# dekatron-sim-4017-a2.net
KiCad netlist of a schematic drawn in EAGLE
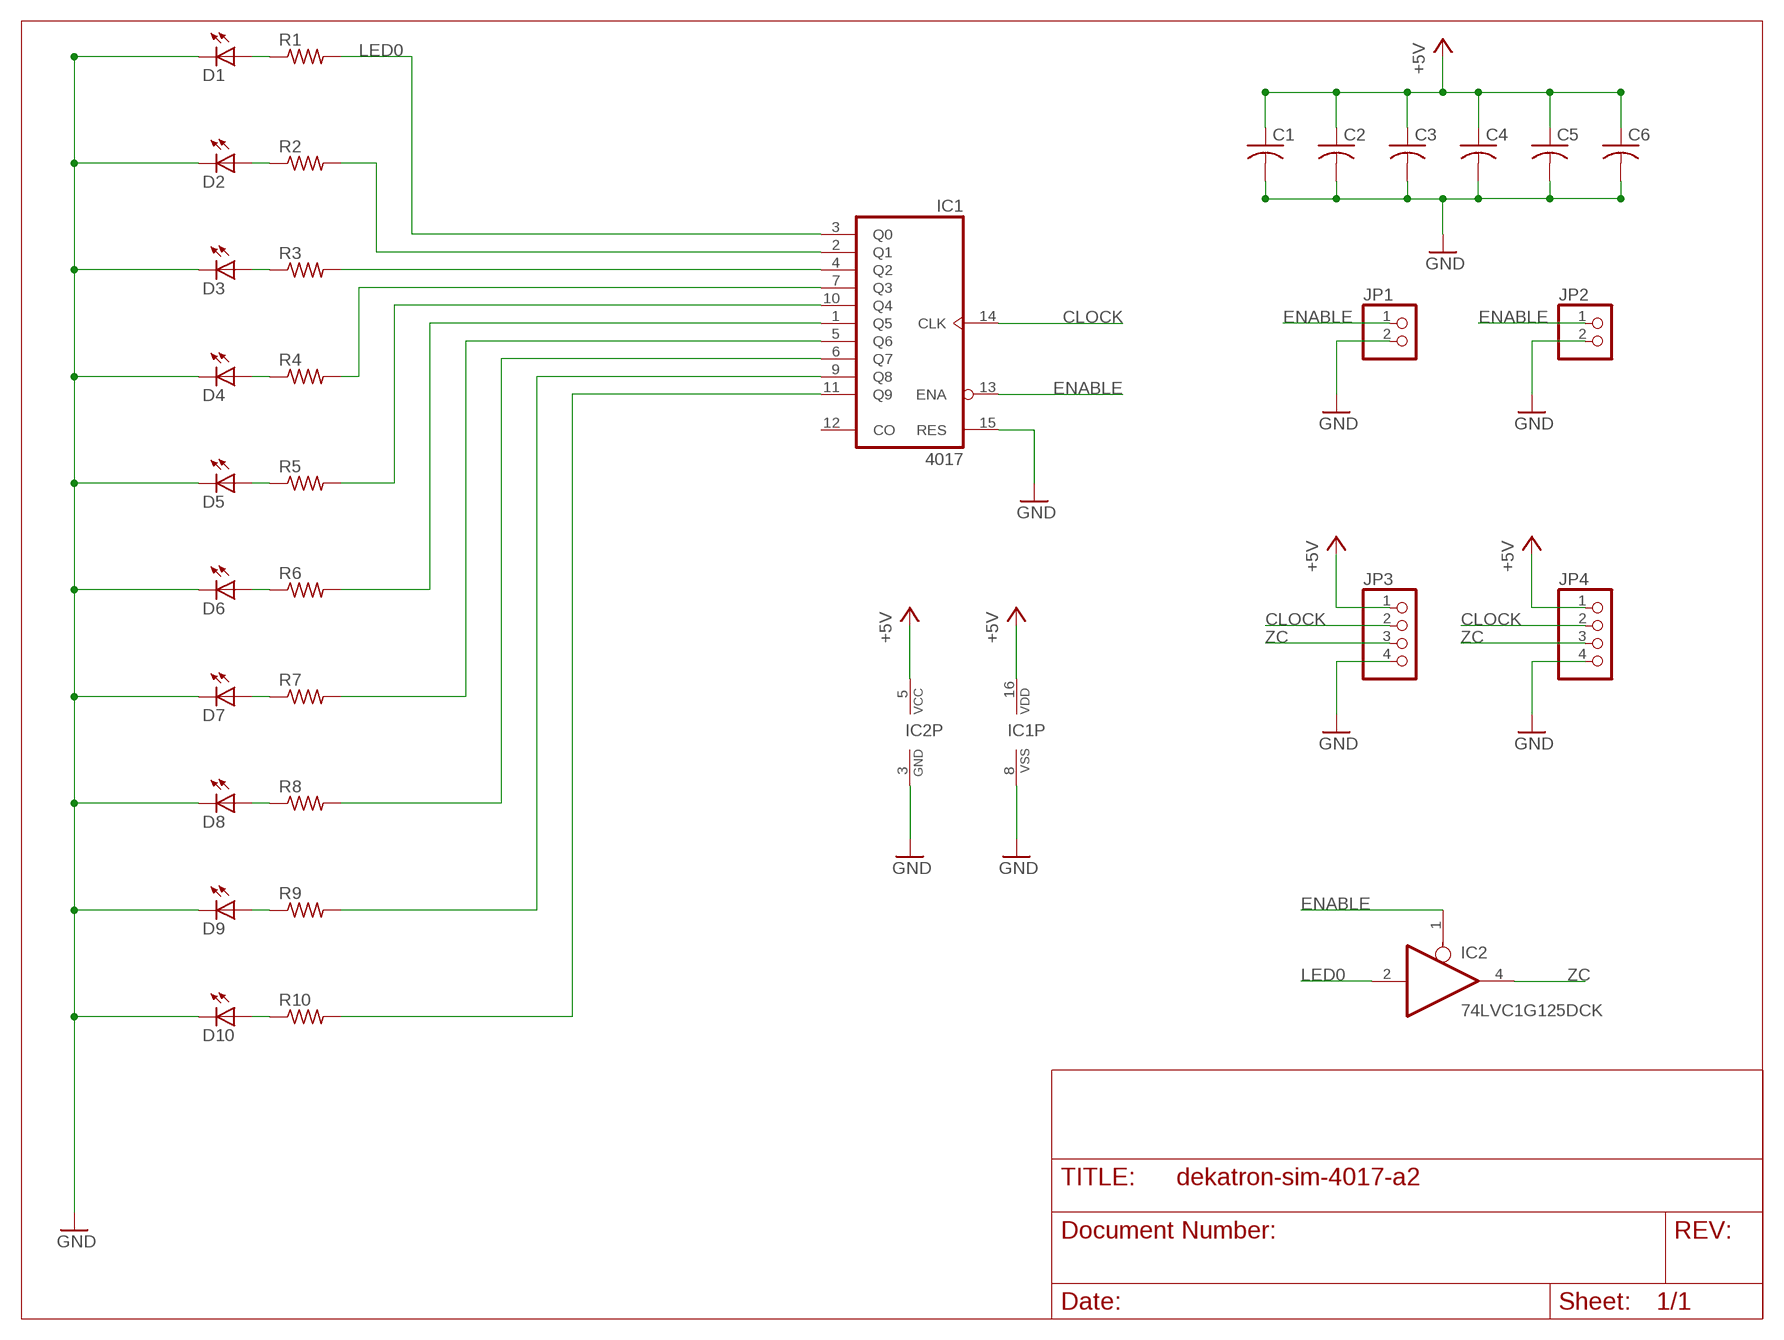
[diagram p0: schematic, sheet 1]

(export (version "E")
  (design (tool "Eeschema 10.0.6"))
  (components
    (comp (ref "C1")
      (value "C-USC0805")
      (footprint "eagle-import:C0805")
      (libsource (lib "eagle-import") (part "C-USC0805"))
    )
    (comp (ref "C2")
      (value "C-USC0805")
      (footprint "eagle-import:C0805")
      (libsource (lib "eagle-import") (part "C-USC0805"))
    )
    (comp (ref "C3")
      (value "C-USC0805")
      (footprint "eagle-import:C0805")
      (libsource (lib "eagle-import") (part "C-USC0805"))
    )
    (comp (ref "C4")
      (value "C-USC0805")
      (footprint "eagle-import:C0805")
      (libsource (lib "eagle-import") (part "C-USC0805"))
    )
    (comp (ref "C5")
      (value "C-USC0805")
      (footprint "eagle-import:C0805")
      (libsource (lib "eagle-import") (part "C-USC0805"))
    )
    (comp (ref "C6")
      (value "C-USC0805")
      (footprint "eagle-import:C0805")
      (libsource (lib "eagle-import") (part "C-USC0805"))
    )
    (comp (ref "D1")
      (value "RED")
      (footprint "eagle-import:CHIP-LED0603")
      (libsource (lib "eagle-import") (part "LEDCHIP-LED0603"))
    )
    (comp (ref "D2")
      (value "RED")
      (footprint "eagle-import:CHIP-LED0603")
      (libsource (lib "eagle-import") (part "LEDCHIP-LED0603"))
    )
    (comp (ref "D3")
      (value "RED")
      (footprint "eagle-import:CHIP-LED0603")
      (libsource (lib "eagle-import") (part "LEDCHIP-LED0603"))
    )
    (comp (ref "D4")
      (value "RED")
      (footprint "eagle-import:CHIP-LED0603")
      (libsource (lib "eagle-import") (part "LEDCHIP-LED0603"))
    )
    (comp (ref "D5")
      (value "RED")
      (footprint "eagle-import:CHIP-LED0603")
      (libsource (lib "eagle-import") (part "LEDCHIP-LED0603"))
    )
    (comp (ref "D6")
      (value "RED")
      (footprint "eagle-import:CHIP-LED0603")
      (libsource (lib "eagle-import") (part "LEDCHIP-LED0603"))
    )
    (comp (ref "D7")
      (value "RED")
      (footprint "eagle-import:CHIP-LED0603")
      (libsource (lib "eagle-import") (part "LEDCHIP-LED0603"))
    )
    (comp (ref "D8")
      (value "RED")
      (footprint "eagle-import:CHIP-LED0603")
      (libsource (lib "eagle-import") (part "LEDCHIP-LED0603"))
    )
    (comp (ref "D9")
      (value "RED")
      (footprint "eagle-import:CHIP-LED0603")
      (libsource (lib "eagle-import") (part "LEDCHIP-LED0603"))
    )
    (comp (ref "D10")
      (value "RED")
      (footprint "eagle-import:CHIP-LED0603")
      (libsource (lib "eagle-import") (part "LEDCHIP-LED0603"))
    )
    (comp (ref "IC1")
      (value "4017")
      (footprint "eagle-import:TSSOP16")
      (libsource (lib "eagle-import") (part "4017"))
    )
    (comp (ref "IC2")
      (value "74LVC1G125DCK")
      (footprint "eagle-import:SC70-5")
      (libsource (lib "eagle-import") (part "741G125DCKLVC"))
    )
    (comp (ref "JP1")
      (value "PINHD-1X2")
      (footprint "eagle-import:1X02")
      (libsource (lib "eagle-import") (part "PINHD-1X2"))
    )
    (comp (ref "JP2")
      (value "PINHD-1X2")
      (footprint "eagle-import:1X02")
      (libsource (lib "eagle-import") (part "PINHD-1X2"))
    )
    (comp (ref "JP3")
      (value "PINHD-1X4")
      (footprint "eagle-import:1X04")
      (libsource (lib "eagle-import") (part "PINHD-1X4"))
    )
    (comp (ref "JP4")
      (value "PINHD-1X4")
      (footprint "eagle-import:1X04")
      (libsource (lib "eagle-import") (part "PINHD-1X4"))
    )
    (comp (ref "R1")
      (value "R-US_R0603")
      (footprint "eagle-import:R0603")
      (libsource (lib "eagle-import") (part "R-US_R0603"))
    )
    (comp (ref "R2")
      (value "R-US_R0603")
      (footprint "eagle-import:R0603")
      (libsource (lib "eagle-import") (part "R-US_R0603"))
    )
    (comp (ref "R3")
      (value "R-US_R0603")
      (footprint "eagle-import:R0603")
      (libsource (lib "eagle-import") (part "R-US_R0603"))
    )
    (comp (ref "R4")
      (value "R-US_R0603")
      (footprint "eagle-import:R0603")
      (libsource (lib "eagle-import") (part "R-US_R0603"))
    )
    (comp (ref "R5")
      (value "R-US_R0603")
      (footprint "eagle-import:R0603")
      (libsource (lib "eagle-import") (part "R-US_R0603"))
    )
    (comp (ref "R6")
      (value "R-US_R0603")
      (footprint "eagle-import:R0603")
      (libsource (lib "eagle-import") (part "R-US_R0603"))
    )
    (comp (ref "R7")
      (value "R-US_R0603")
      (footprint "eagle-import:R0603")
      (libsource (lib "eagle-import") (part "R-US_R0603"))
    )
    (comp (ref "R8")
      (value "R-US_R0603")
      (footprint "eagle-import:R0603")
      (libsource (lib "eagle-import") (part "R-US_R0603"))
    )
    (comp (ref "R9")
      (value "R-US_R0603")
      (footprint "eagle-import:R0603")
      (libsource (lib "eagle-import") (part "R-US_R0603"))
    )
    (comp (ref "R10")
      (value "R-US_R0603")
      (footprint "eagle-import:R0603")
      (libsource (lib "eagle-import") (part "R-US_R0603"))
    )
  )
  (nets
    (net (code "1") (name "+5V") (class "Default")
      (node (ref "C1") (pin "1") (pinfunction "1_1") (pintype "passive"))
      (node (ref "C2") (pin "1") (pinfunction "1_1") (pintype "passive"))
      (node (ref "C3") (pin "1") (pinfunction "1_1") (pintype "passive"))
      (node (ref "C4") (pin "1") (pinfunction "1_1") (pintype "passive"))
      (node (ref "C5") (pin "1") (pinfunction "1_1") (pintype "passive"))
      (node (ref "C6") (pin "1") (pinfunction "1_1") (pintype "passive"))
      (node (ref "IC1") (pin "16") (pinfunction "VDD_16") (pintype "power_in"))
      (node (ref "IC2") (pin "5") (pinfunction "VCC_5") (pintype "power_in"))
      (node (ref "JP3") (pin "1") (pinfunction "1_1") (pintype "passive"))
      (node (ref "JP4") (pin "1") (pinfunction "1_1") (pintype "passive"))
    )
    (net (code "2") (name "/CLOCK") (class "Default")
      (node (ref "IC1") (pin "14") (pinfunction "CLK_14") (pintype "input"))
      (node (ref "JP3") (pin "2") (pinfunction "2_2") (pintype "passive"))
      (node (ref "JP4") (pin "2") (pinfunction "2_2") (pintype "passive"))
    )
    (net (code "3") (name "/ENABLE") (class "Default")
      (node (ref "IC1") (pin "13") (pinfunction "ENA_13") (pintype "input"))
      (node (ref "IC2") (pin "1") (pinfunction "OE_1") (pintype "input"))
      (node (ref "JP1") (pin "1") (pinfunction "1_1") (pintype "passive"))
      (node (ref "JP2") (pin "1") (pinfunction "1_1") (pintype "passive"))
    )
    (net (code "4") (name "/LED0") (class "Default")
      (node (ref "IC1") (pin "3") (pinfunction "Q0_3") (pintype "output"))
      (node (ref "IC2") (pin "2") (pinfunction "I_2") (pintype "input"))
      (node (ref "R1") (pin "2") (pinfunction "2_2") (pintype "passive"))
    )
    (net (code "5") (name "/ZC") (class "Default")
      (node (ref "IC2") (pin "4") (pinfunction "O_4") (pintype "tri_state"))
      (node (ref "JP3") (pin "3") (pinfunction "3_3") (pintype "passive"))
      (node (ref "JP4") (pin "3") (pinfunction "3_3") (pintype "passive"))
    )
    (net (code "6") (name "GND") (class "Default")
      (node (ref "C1") (pin "2") (pinfunction "2_2") (pintype "passive"))
      (node (ref "C2") (pin "2") (pinfunction "2_2") (pintype "passive"))
      (node (ref "C3") (pin "2") (pinfunction "2_2") (pintype "passive"))
      (node (ref "C4") (pin "2") (pinfunction "2_2") (pintype "passive"))
      (node (ref "C5") (pin "2") (pinfunction "2_2") (pintype "passive"))
      (node (ref "C6") (pin "2") (pinfunction "2_2") (pintype "passive"))
      (node (ref "D1") (pin "C") (pinfunction "C_C") (pintype "passive"))
      (node (ref "D10") (pin "C") (pinfunction "C_C") (pintype "passive"))
      (node (ref "D2") (pin "C") (pinfunction "C_C") (pintype "passive"))
      (node (ref "D3") (pin "C") (pinfunction "C_C") (pintype "passive"))
      (node (ref "D4") (pin "C") (pinfunction "C_C") (pintype "passive"))
      (node (ref "D5") (pin "C") (pinfunction "C_C") (pintype "passive"))
      (node (ref "D6") (pin "C") (pinfunction "C_C") (pintype "passive"))
      (node (ref "D7") (pin "C") (pinfunction "C_C") (pintype "passive"))
      (node (ref "D8") (pin "C") (pinfunction "C_C") (pintype "passive"))
      (node (ref "D9") (pin "C") (pinfunction "C_C") (pintype "passive"))
      (node (ref "IC1") (pin "15") (pinfunction "RES_15") (pintype "input"))
      (node (ref "IC1") (pin "8") (pinfunction "VSS_8") (pintype "power_in"))
      (node (ref "IC2") (pin "3") (pinfunction "GND_3") (pintype "power_in"))
      (node (ref "JP1") (pin "2") (pinfunction "2_2") (pintype "passive"))
      (node (ref "JP2") (pin "2") (pinfunction "2_2") (pintype "passive"))
      (node (ref "JP3") (pin "4") (pinfunction "4_4") (pintype "passive"))
      (node (ref "JP4") (pin "4") (pinfunction "4_4") (pintype "passive"))
    )
    (net (code "7") (name "Net-(D1-PadA)") (class "Default")
      (node (ref "D1") (pin "A") (pinfunction "A_A") (pintype "passive"))
      (node (ref "R1") (pin "1") (pinfunction "1_1") (pintype "passive"))
    )
    (net (code "8") (name "Net-(D2-PadA)") (class "Default")
      (node (ref "D2") (pin "A") (pinfunction "A_A") (pintype "passive"))
      (node (ref "R2") (pin "1") (pinfunction "1_1") (pintype "passive"))
    )
    (net (code "9") (name "Net-(D3-PadA)") (class "Default")
      (node (ref "D3") (pin "A") (pinfunction "A_A") (pintype "passive"))
      (node (ref "R3") (pin "1") (pinfunction "1_1") (pintype "passive"))
    )
    (net (code "10") (name "Net-(D4-PadA)") (class "Default")
      (node (ref "D4") (pin "A") (pinfunction "A_A") (pintype "passive"))
      (node (ref "R4") (pin "1") (pinfunction "1_1") (pintype "passive"))
    )
    (net (code "11") (name "Net-(D5-PadA)") (class "Default")
      (node (ref "D5") (pin "A") (pinfunction "A_A") (pintype "passive"))
      (node (ref "R5") (pin "1") (pinfunction "1_1") (pintype "passive"))
    )
    (net (code "12") (name "Net-(D6-PadA)") (class "Default")
      (node (ref "D6") (pin "A") (pinfunction "A_A") (pintype "passive"))
      (node (ref "R6") (pin "1") (pinfunction "1_1") (pintype "passive"))
    )
    (net (code "13") (name "Net-(D7-PadA)") (class "Default")
      (node (ref "D7") (pin "A") (pinfunction "A_A") (pintype "passive"))
      (node (ref "R7") (pin "1") (pinfunction "1_1") (pintype "passive"))
    )
    (net (code "14") (name "Net-(D8-PadA)") (class "Default")
      (node (ref "D8") (pin "A") (pinfunction "A_A") (pintype "passive"))
      (node (ref "R8") (pin "1") (pinfunction "1_1") (pintype "passive"))
    )
    (net (code "15") (name "Net-(D9-PadA)") (class "Default")
      (node (ref "D9") (pin "A") (pinfunction "A_A") (pintype "passive"))
      (node (ref "R9") (pin "1") (pinfunction "1_1") (pintype "passive"))
    )
    (net (code "16") (name "Net-(D10-PadA)") (class "Default")
      (node (ref "D10") (pin "A") (pinfunction "A_A") (pintype "passive"))
      (node (ref "R10") (pin "1") (pinfunction "1_1") (pintype "passive"))
    )
    (net (code "17") (name "Net-(IC1A-Q1)") (class "Default")
      (node (ref "IC1") (pin "2") (pinfunction "Q1_2") (pintype "output"))
      (node (ref "R2") (pin "2") (pinfunction "2_2") (pintype "passive"))
    )
    (net (code "18") (name "Net-(IC1A-Q2)") (class "Default")
      (node (ref "IC1") (pin "4") (pinfunction "Q2_4") (pintype "output"))
      (node (ref "R3") (pin "2") (pinfunction "2_2") (pintype "passive"))
    )
    (net (code "19") (name "Net-(IC1A-Q3)") (class "Default")
      (node (ref "IC1") (pin "7") (pinfunction "Q3_7") (pintype "output"))
      (node (ref "R4") (pin "2") (pinfunction "2_2") (pintype "passive"))
    )
    (net (code "20") (name "Net-(IC1A-Q4)") (class "Default")
      (node (ref "IC1") (pin "10") (pinfunction "Q4_10") (pintype "output"))
      (node (ref "R5") (pin "2") (pinfunction "2_2") (pintype "passive"))
    )
    (net (code "21") (name "Net-(IC1A-Q5)") (class "Default")
      (node (ref "IC1") (pin "1") (pinfunction "Q5_1") (pintype "output"))
      (node (ref "R6") (pin "2") (pinfunction "2_2") (pintype "passive"))
    )
    (net (code "22") (name "Net-(IC1A-Q6)") (class "Default")
      (node (ref "IC1") (pin "5") (pinfunction "Q6_5") (pintype "output"))
      (node (ref "R7") (pin "2") (pinfunction "2_2") (pintype "passive"))
    )
    (net (code "23") (name "Net-(IC1A-Q7)") (class "Default")
      (node (ref "IC1") (pin "6") (pinfunction "Q7_6") (pintype "output"))
      (node (ref "R8") (pin "2") (pinfunction "2_2") (pintype "passive"))
    )
    (net (code "24") (name "Net-(IC1A-Q8)") (class "Default")
      (node (ref "IC1") (pin "9") (pinfunction "Q8_9") (pintype "output"))
      (node (ref "R9") (pin "2") (pinfunction "2_2") (pintype "passive"))
    )
    (net (code "25") (name "Net-(IC1A-Q9)") (class "Default")
      (node (ref "IC1") (pin "11") (pinfunction "Q9_11") (pintype "output"))
      (node (ref "R10") (pin "2") (pinfunction "2_2") (pintype "passive"))
    )
    (net (code "26") (name "unconnected-(IC1A-CO-Pad12)") (class "Default")
      (node (ref "IC1") (pin "12") (pinfunction "CO_12") (pintype "output"))
    )
  )
)
